# Breakout.net
KiCad netlist of a schematic drawn in Altium Designer
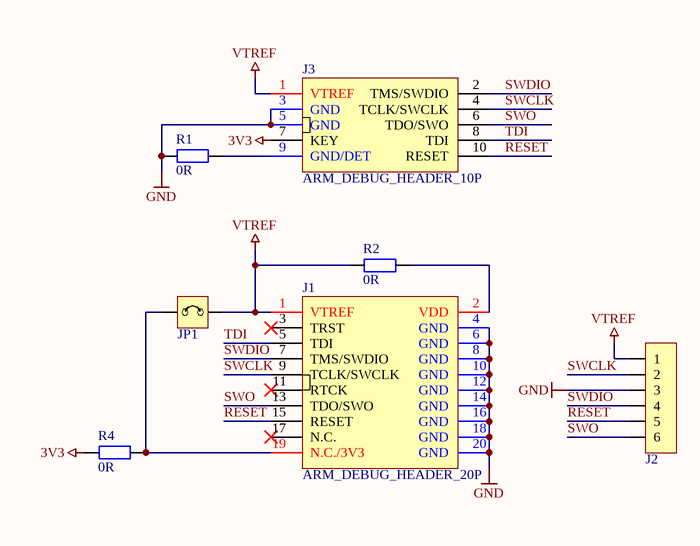
[diagram p0: Breakout.SchDoc]

(export (version "E")
  (design (tool "Eeschema 10.0.6"))
  (components
    (comp (ref "J1")
      (value "ARM_DEBUG_HEADER_20P")
      (footprint "AG.Connectors:ARM_STD_20P_HEADER-2.54-20P2")
      (description "ARM Standard 20-Pin Header")
      (libsource (lib "AG.Connectors") (part "ARM_DEBUG_HEADER_20P"))
    )
    (comp (ref "J2")
      (value "PINHDR-6P1")
      (footprint "HEADER-2.54-6P1")
      (description "Pin Header Single Row 6 Positions")
      (libsource (lib "AG.Connectors") (part "PINHDR-6P1"))
    )
    (comp (ref "J3")
      (value "ARM_DEBUG_HEADER_10P")
      (footprint "AG.Connectors:ARM_CORTEX_DEBUG_HEADER-1.27-10P-2R")
      (description "ARM Cortex Debug 10-Pin Header")
      (libsource (lib "AG.Connectors") (part "ARM_DEBUG_HEADER_10P"))
    )
    (comp (ref "JP1")
      (value "ON/OFF")
      (footprint "AG.Connectors:HEADER-2.54-2P1")
      (description "Jumper (SPST/ON-OFF)")
      (libsource (lib "AG.Connectors") (part "JP-SPST"))
    )
    (comp (ref "R1")
      (value "0R")
      (footprint "Chip:R0603_RF_M")
      (description "Resistor")
      (fields (field (name "TOLERANCE") "?") (field (name "MANUFACTURER") "Generic Brand"))
      (libsource (lib "AG.Generic") (part "R"))
    )
    (comp (ref "R2")
      (value "0R")
      (footprint "Chip:R0603_RF_M")
      (description "Resistor")
      (fields (field (name "TOLERANCE") "?") (field (name "MANUFACTURER") "Generic Brand"))
      (libsource (lib "AG.Generic") (part "R"))
    )
    (comp (ref "R4")
      (value "0R")
      (footprint "Chip:R0603_RF_M")
      (description "Resistor")
      (fields (field (name "TOLERANCE") "?") (field (name "MANUFACTURER") "Generic Brand"))
      (libsource (lib "AG.Generic") (part "R"))
    )
  )
  (nets
    (net (code "1") (name "/RESET") (class "Default")
      (node (ref "J1") (pin "15") (pinfunction "RESET_15") (pintype "passive"))
      (node (ref "J2") (pin "5") (pinfunction "5_5") (pintype "passive"))
      (node (ref "J3") (pin "10") (pinfunction "RESET_10") (pintype "passive"))
    )
    (net (code "2") (name "/SWCLK") (class "Default")
      (node (ref "J1") (pin "9") (pinfunction "TCLK/SWCLK_9") (pintype "passive"))
      (node (ref "J2") (pin "2") (pinfunction "2_2") (pintype "passive"))
      (node (ref "J3") (pin "4") (pinfunction "TCLK/SWCLK_4") (pintype "passive"))
    )
    (net (code "3") (name "/SWDIO") (class "Default")
      (node (ref "J1") (pin "7") (pinfunction "TMS/SWDIO_7") (pintype "passive"))
      (node (ref "J2") (pin "4") (pinfunction "4_4") (pintype "passive"))
      (node (ref "J3") (pin "2") (pinfunction "TMS/SWDIO_2") (pintype "passive"))
    )
    (net (code "4") (name "/SWO") (class "Default")
      (node (ref "J1") (pin "13") (pinfunction "TDO/SWO_13") (pintype "passive"))
      (node (ref "J2") (pin "6") (pinfunction "6_6") (pintype "passive"))
      (node (ref "J3") (pin "6") (pinfunction "TDO/SWO_6") (pintype "passive"))
    )
    (net (code "5") (name "/TDI") (class "Default")
      (node (ref "J1") (pin "5") (pinfunction "TDI_5") (pintype "passive"))
      (node (ref "J3") (pin "8") (pinfunction "TDI_8") (pintype "passive"))
    )
    (net (code "6") (name "3V3") (class "Default")
      (node (ref "J3") (pin "7") (pinfunction "KEY_7") (pintype "passive"))
      (node (ref "R4") (pin "1") (pintype "passive"))
    )
    (net (code "7") (name "GND") (class "Default")
      (node (ref "J1") (pin "10") (pinfunction "GND_10") (pintype "passive"))
      (node (ref "J1") (pin "12") (pinfunction "GND_12") (pintype "passive"))
      (node (ref "J1") (pin "14") (pinfunction "GND_14") (pintype "passive"))
      (node (ref "J1") (pin "16") (pinfunction "GND_16") (pintype "passive"))
      (node (ref "J1") (pin "18") (pinfunction "GND_18") (pintype "passive"))
      (node (ref "J1") (pin "20") (pinfunction "GND_20") (pintype "passive"))
      (node (ref "J1") (pin "4") (pinfunction "GND_4") (pintype "passive"))
      (node (ref "J1") (pin "6") (pinfunction "GND_6") (pintype "passive"))
      (node (ref "J1") (pin "8") (pinfunction "GND_8") (pintype "passive"))
      (node (ref "J2") (pin "3") (pinfunction "3_3") (pintype "passive"))
      (node (ref "J3") (pin "3") (pinfunction "GND_3") (pintype "passive"))
      (node (ref "J3") (pin "5") (pinfunction "GND_5") (pintype "passive"))
      (node (ref "R1") (pin "1") (pintype "passive"))
    )
    (net (code "8") (name "Net-(J1-N.C.{slash}3V3)") (class "Default")
      (node (ref "J1") (pin "19") (pinfunction "N.C./3V3_19") (pintype "passive"))
      (node (ref "JP1") (pin "1") (pinfunction "1_1") (pintype "passive"))
      (node (ref "R4") (pin "2") (pintype "passive"))
    )
    (net (code "9") (name "Net-(J1-VDD)") (class "Default")
      (node (ref "J1") (pin "2") (pinfunction "VDD_2") (pintype "passive"))
      (node (ref "R2") (pin "2") (pintype "passive"))
    )
    (net (code "10") (name "Net-(J3-GND{slash}DET)") (class "Default")
      (node (ref "J3") (pin "9") (pinfunction "GND/DET_9") (pintype "passive"))
      (node (ref "R1") (pin "2") (pintype "passive"))
    )
    (net (code "11") (name "VTREF") (class "Default")
      (node (ref "J1") (pin "1") (pinfunction "VTREF_1") (pintype "passive"))
      (node (ref "J2") (pin "1") (pinfunction "1_1") (pintype "passive"))
      (node (ref "J3") (pin "1") (pinfunction "VTREF_1") (pintype "passive"))
      (node (ref "JP1") (pin "2") (pinfunction "2_2") (pintype "passive"))
      (node (ref "R2") (pin "1") (pintype "passive"))
    )
    (net (code "12") (name "unconnected-(J1-N.C.-Pad17)") (class "Default")
      (node (ref "J1") (pin "17") (pinfunction "N.C._17") (pintype "passive+no_connect"))
    )
    (net (code "13") (name "unconnected-(J1-RTCK-Pad11)") (class "Default")
      (node (ref "J1") (pin "11") (pinfunction "RTCK_11") (pintype "passive+no_connect"))
    )
    (net (code "14") (name "unconnected-(J1-TRST-Pad3)") (class "Default")
      (node (ref "J1") (pin "3") (pinfunction "TRST_3") (pintype "passive+no_connect"))
    )
  )
)
